# bjt-ce.net
KiCad netlist of a schematic drawn in EAGLE
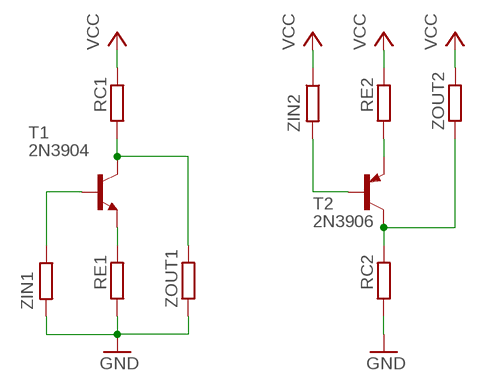
[diagram p0: schematic, sheet 1]

(export (version "E")
  (design (tool "Eeschema 10.0.6"))
  (components
    (comp (ref "RC1")
      (value "R-EU_0207/10")
      (footprint "eagle-import:0207_10")
      (libsource (lib "eagle-import") (part "R-EU_0207/10"))
    )
    (comp (ref "RC2")
      (value "R-EU_0207/10")
      (footprint "eagle-import:0207_10")
      (libsource (lib "eagle-import") (part "R-EU_0207/10"))
    )
    (comp (ref "RE1")
      (value "R-EU_0207/10")
      (footprint "eagle-import:0207_10")
      (libsource (lib "eagle-import") (part "R-EU_0207/10"))
    )
    (comp (ref "RE2")
      (value "R-EU_0207/10")
      (footprint "eagle-import:0207_10")
      (libsource (lib "eagle-import") (part "R-EU_0207/10"))
    )
    (comp (ref "T1")
      (value "2N3904")
      (footprint "eagle-import:TO92")
      (libsource (lib "eagle-import") (part "2N3904"))
    )
    (comp (ref "T2")
      (value "2N3906")
      (footprint "eagle-import:TO92")
      (libsource (lib "eagle-import") (part "2N3906"))
    )
    (comp (ref "ZIN1")
      (value "R-EU_0207/10")
      (footprint "eagle-import:0207_10")
      (libsource (lib "eagle-import") (part "R-EU_0207/10"))
    )
    (comp (ref "ZIN2")
      (value "R-EU_0207/10")
      (footprint "eagle-import:0207_10")
      (libsource (lib "eagle-import") (part "R-EU_0207/10"))
    )
    (comp (ref "ZOUT1")
      (value "R-EU_0207/10")
      (footprint "eagle-import:0207_10")
      (libsource (lib "eagle-import") (part "R-EU_0207/10"))
    )
    (comp (ref "ZOUT2")
      (value "R-EU_0207/10")
      (footprint "eagle-import:0207_10")
      (libsource (lib "eagle-import") (part "R-EU_0207/10"))
    )
  )
  (nets
    (net (code "1") (name "GND") (class "Default")
      (node (ref "RC2") (pin "1") (pinfunction "1_1") (pintype "passive"))
      (node (ref "RE1") (pin "1") (pinfunction "1_1") (pintype "passive"))
      (node (ref "ZIN1") (pin "2") (pinfunction "2_2") (pintype "passive"))
      (node (ref "ZOUT1") (pin "1") (pinfunction "1_1") (pintype "passive"))
    )
    (net (code "2") (name "Net-(T1-B)") (class "Default")
      (node (ref "T1") (pin "2") (pinfunction "B_2") (pintype "passive"))
      (node (ref "ZIN1") (pin "1") (pinfunction "1_1") (pintype "passive"))
    )
    (net (code "3") (name "Net-(T1-C)") (class "Default")
      (node (ref "RC1") (pin "1") (pinfunction "1_1") (pintype "passive"))
      (node (ref "T1") (pin "1") (pinfunction "C_1") (pintype "passive"))
      (node (ref "ZOUT1") (pin "2") (pinfunction "2_2") (pintype "passive"))
    )
    (net (code "4") (name "Net-(T1-E)") (class "Default")
      (node (ref "RE1") (pin "2") (pinfunction "2_2") (pintype "passive"))
      (node (ref "T1") (pin "3") (pinfunction "E_3") (pintype "passive"))
    )
    (net (code "5") (name "Net-(T2-B)") (class "Default")
      (node (ref "T2") (pin "2") (pinfunction "B_2") (pintype "passive"))
      (node (ref "ZIN2") (pin "2") (pinfunction "2_2") (pintype "passive"))
    )
    (net (code "6") (name "Net-(T2-C)") (class "Default")
      (node (ref "RC2") (pin "2") (pinfunction "2_2") (pintype "passive"))
      (node (ref "T2") (pin "1") (pinfunction "C_1") (pintype "passive"))
      (node (ref "ZOUT2") (pin "1") (pinfunction "1_1") (pintype "passive"))
    )
    (net (code "7") (name "Net-(T2-E)") (class "Default")
      (node (ref "RE2") (pin "1") (pinfunction "1_1") (pintype "passive"))
      (node (ref "T2") (pin "3") (pinfunction "E_3") (pintype "passive"))
    )
    (net (code "8") (name "VCC") (class "Default")
      (node (ref "RC1") (pin "2") (pinfunction "2_2") (pintype "passive"))
      (node (ref "RE2") (pin "2") (pinfunction "2_2") (pintype "passive"))
      (node (ref "ZIN2") (pin "1") (pinfunction "1_1") (pintype "passive"))
      (node (ref "ZOUT2") (pin "2") (pinfunction "2_2") (pintype "passive"))
    )
  )
)
